# PowerOld.net
KiCad netlist of a schematic drawn in Altium Designer
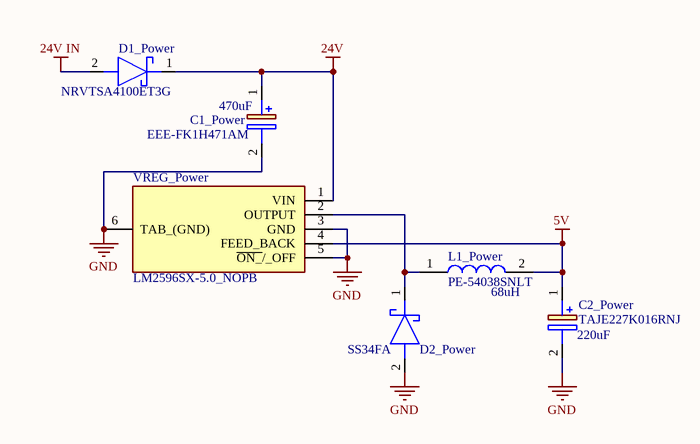
[diagram p0: PowerOld.SchDoc]

(export (version "E")
  (design (tool "Eeschema 10.0.6"))
  (components
    (comp (ref "C1_Power")
      (value "EEE-FK1H471AM")
      (footprint "LX1-Power:CAPAE1700X1700N")
      (description "Capacitor Polarised")
      (fields (field (name "MOUSER PART NUMBER") "667-EEE-FK1H471AM") (field (name "ALTIUM_VALUE") "470uF"))
      (libsource (lib "LX-1-Power") (part "EEE-FK1H471AM"))
    )
    (comp (ref "C2_Power")
      (value "TAJE227K016RNJ")
      (footprint "LX1-Power:CAPPM7344X430N")
      (description "Capacitor Polarised")
      (fields
        (field (name "MOUSER PART NUMBER") "581-TAJE227K016R")
        (field (name "RS PART NUMBER") "1355452P")
        (field (name "ALTIUM_VALUE") "220uF")
      )
      (libsource (lib "LX-1-Power") (part "TAJE227K016RNJ"))
    )
    (comp (ref "D1_Power")
      (value "NRVTSA4100ET3G")
      (footprint "LX1-Power:DIOM5226X220N")
      (description "Schottky Diode")
      (fields
        (field (name "MOUSER PART NUMBER") "863-NRVTSA4100ET3G")
        (field (name "RS PART NUMBER") "1413561P")
      )
      (libsource (lib "LX-1-Power") (part "NRVTSA4100ET3G"))
    )
    (comp (ref "D2_Power")
      (value "SS34FA")
      (footprint "LX1-Power:SODFL3618X143N")
      (description "Schottky Diode")
      (fields (field (name "MOUSER PART NUMBER") "512-SS34FA") (field (name "RS PART NUMBER") "1841417"))
      (libsource (lib "LX-1-Power") (part "SS34FA"))
    )
    (comp (ref "L1_Power")
      (value "PE-54038SNLT")
      (footprint "LX1-Power:HCI-68")
      (description "Inductor")
      (fields
        (field (name "MOUSER PART NUMBER") "673-PE-54038SNLT")
        (field (name "RS PART NUMBER") "7428262")
        (field (name "ALTIUM_VALUE") "68uH")
      )
      (libsource (lib "LX-1-Power") (part "PE-54038SNLT"))
    )
    (comp (ref "VREG_Power")
      (value "LM2596SX-5.0_NOPB")
      (footprint "LX1-Power:KTT0005B")
      (description "Integrated Circuit")
      (fields
        (field (name "MANUFACTURER_PART_NUMBER") "LM2596SX-5.0/NOPB")
        (field (name "MOUSER PART NUMBER") "926-LM2596SX-5.0NOPB")
      )
      (libsource (lib "LX-1-Power") (part "LM2596SX-5.0_NOPB"))
    )
  )
  (nets
    (net (code "1") (name "5V") (class "Default")
      (node (ref "C2_Power") (pin "1") (pinfunction "+_1") (pintype "passive"))
      (node (ref "L1_Power") (pin "2") (pinfunction "2_2") (pintype "passive"))
      (node (ref "VREG_Power") (pin "4") (pinfunction "FEED_BACK_4") (pintype "passive"))
    )
    (net (code "2") (name "24V") (class "Default")
      (node (ref "C1_Power") (pin "1") (pinfunction "+_1") (pintype "passive"))
      (node (ref "D1_Power") (pin "1") (pinfunction "K_1") (pintype "passive"))
      (node (ref "VREG_Power") (pin "1") (pinfunction "VIN_1") (pintype "passive"))
    )
    (net (code "3") (name "24V IN") (class "Default")
      (node (ref "D1_Power") (pin "2") (pinfunction "A_2") (pintype "passive"))
    )
    (net (code "4") (name "GND") (class "Default")
      (node (ref "C1_Power") (pin "2") (pinfunction "-_2") (pintype "passive"))
      (node (ref "C2_Power") (pin "2") (pinfunction "-_2") (pintype "passive"))
      (node (ref "D2_Power") (pin "2") (pinfunction "A_2") (pintype "passive"))
      (node (ref "VREG_Power") (pin "3") (pinfunction "GND_3") (pintype "passive"))
      (node (ref "VREG_Power") (pin "5") (pinfunction "~{ON_}/_OFF_5") (pintype "passive"))
      (node (ref "VREG_Power") (pin "6") (pinfunction "TAB_(GND)_6") (pintype "passive"))
    )
    (net (code "5") (name "Net-(D2_Power-K)") (class "Default")
      (node (ref "D2_Power") (pin "1") (pinfunction "K_1") (pintype "passive"))
      (node (ref "L1_Power") (pin "1") (pinfunction "1_1") (pintype "passive"))
      (node (ref "VREG_Power") (pin "2") (pinfunction "OUTPUT_2") (pintype "passive"))
    )
  )
)
